# URC.net
KiCad netlist of a schematic drawn in EAGLE
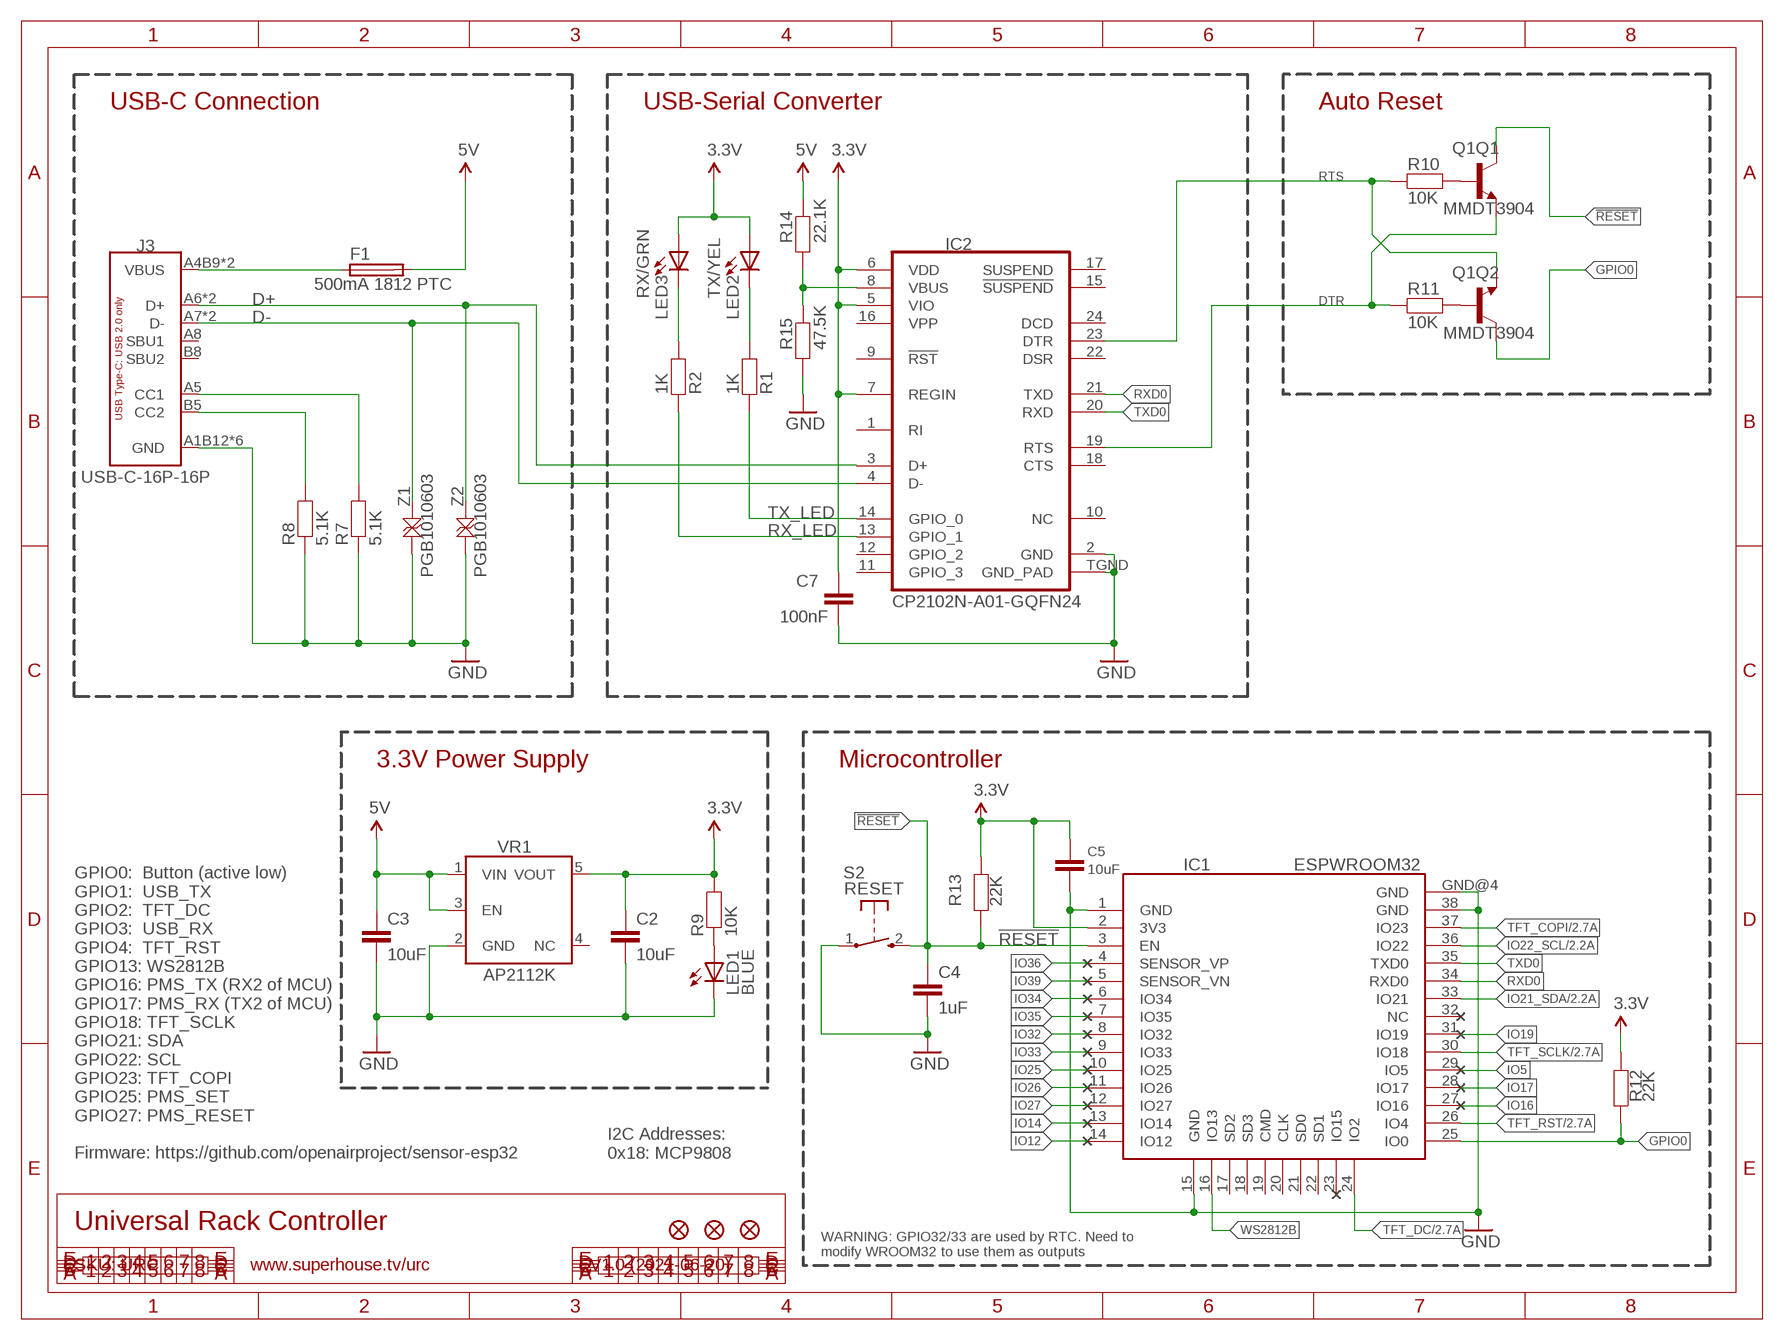
[diagram p0: schematic, sheet 1]
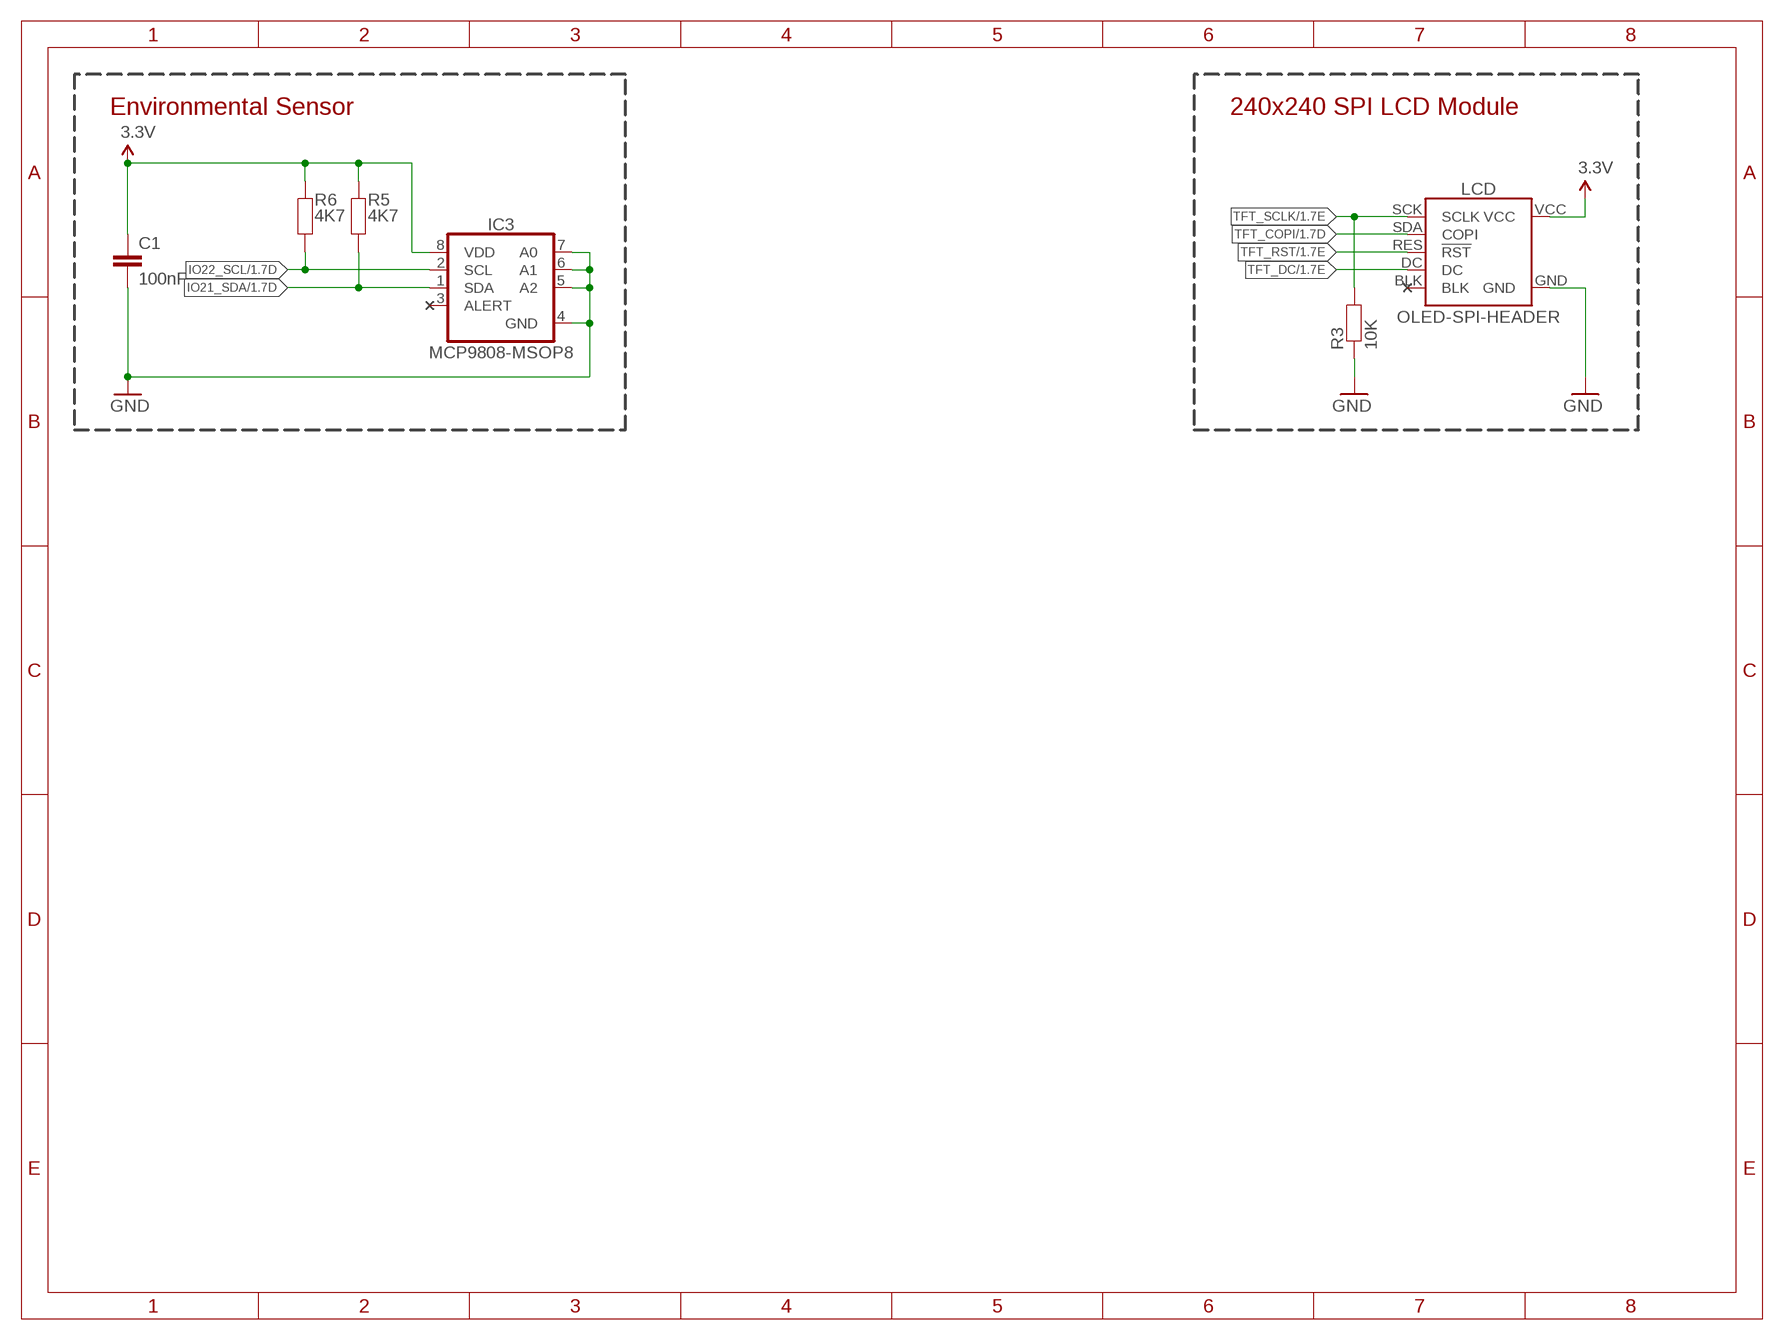
[diagram p1: schematic, sheet 2]

(export (version "E")
  (design (tool "Eeschema 10.0.6"))
  (components
    (comp (ref "C1")
      (value "100nF")
      (footprint "eagle-import:C0603")
      (libsource (lib "eagle-import") (part "CAP0603"))
    )
    (comp (ref "IC3")
      (value "MCP9808-MSOP8")
      (footprint "eagle-import:MSOP-8")
      (libsource (lib "eagle-import") (part "MCP9808-MSOP8"))
    )
    (comp (ref "LCD")
      (value "OLED-SPI-HEADER")
      (footprint "eagle-import:OLED-240X240-1.3-HEADER")
      (libsource (lib "eagle-import") (part "OLED-SPI-HEADER"))
    )
    (comp (ref "R3")
      (value "10K")
      (footprint "eagle-import:R0603")
      (libsource (lib "eagle-import") (part "SuperHouse-Resistors_28961094_RESISTOR0603"))
    )
    (comp (ref "R5")
      (value "4K7")
      (footprint "eagle-import:R0603")
      (libsource (lib "eagle-import") (part "RESISTOR0603"))
    )
    (comp (ref "R6")
      (value "4K7")
      (footprint "eagle-import:R0603")
      (libsource (lib "eagle-import") (part "RESISTOR0603"))
    )
    (comp (ref "C2")
      (value "10uF")
      (footprint "eagle-import:C0805")
      (libsource (lib "eagle-import") (part "CAP0805"))
    )
    (comp (ref "C3")
      (value "10uF")
      (footprint "eagle-import:C0805")
      (libsource (lib "eagle-import") (part "CAP0805"))
    )
    (comp (ref "C4")
      (value "1uF")
      (footprint "eagle-import:C0603")
      (libsource (lib "eagle-import") (part "CAP0603"))
    )
    (comp (ref "C5")
      (value "10uF")
      (footprint "eagle-import:C0805")
      (libsource (lib "eagle-import") (part "CAP0805"))
    )
    (comp (ref "C7")
      (value "100nF")
      (footprint "eagle-import:C0603")
      (libsource (lib "eagle-import") (part "CAP0603"))
    )
    (comp (ref "F1")
      (value "500mA 1812 PTC")
      (footprint "eagle-import:1812")
      (libsource (lib "eagle-import") (part "PTC050"))
    )
    (comp (ref "IC1")
      (value "ESPWROOM32")
      (footprint "eagle-import:ESPWROOM32")
      (libsource (lib "eagle-import") (part "ESPWROOM32"))
    )
    (comp (ref "IC2")
      (value "CP2102N-A01-GQFN24")
      (footprint "eagle-import:QFN-24")
      (libsource (lib "eagle-import") (part "CP2104"))
    )
    (comp (ref "J3")
      (value "USB-C-16P-16P")
      (footprint "eagle-import:USB-C-16P")
      (libsource (lib "eagle-import") (part "USB-C-16P-16P"))
    )
    (comp (ref "LED1")
      (value "BLUE")
      (footprint "eagle-import:LED-0603")
      (libsource (lib "eagle-import") (part "LED0603"))
    )
    (comp (ref "LED2")
      (value "TX/YEL")
      (footprint "eagle-import:LED-0603")
      (libsource (lib "eagle-import") (part "LED0603"))
    )
    (comp (ref "LED3")
      (value "RX/GRN")
      (footprint "eagle-import:LED-0603")
      (libsource (lib "eagle-import") (part "LED0603"))
    )
    (comp (ref "Q1")
      (value "MMDT3904")
      (footprint "eagle-import:SOT-363")
      (libsource (lib "eagle-import") (part "TRANS_NPN_DUAL-MMDT3904"))
    )
    (comp (ref "R1")
      (value "1K")
      (footprint "eagle-import:R0603")
      (libsource (lib "eagle-import") (part "RESISTOR0603"))
    )
    (comp (ref "R2")
      (value "1K")
      (footprint "eagle-import:R0603")
      (libsource (lib "eagle-import") (part "RESISTOR0603"))
    )
    (comp (ref "R7")
      (value "5.1K")
      (footprint "eagle-import:R0603")
      (libsource (lib "eagle-import") (part "RESISTOR0603"))
    )
    (comp (ref "R8")
      (value "5.1K")
      (footprint "eagle-import:R0603")
      (libsource (lib "eagle-import") (part "RESISTOR0603"))
    )
    (comp (ref "R9")
      (value "10K")
      (footprint "eagle-import:R0603")
      (libsource (lib "eagle-import") (part "RESISTOR0603"))
    )
    (comp (ref "R10")
      (value "10K")
      (footprint "eagle-import:R0603")
      (libsource (lib "eagle-import") (part "RESISTOR0603"))
    )
    (comp (ref "R11")
      (value "10K")
      (footprint "eagle-import:R0603")
      (libsource (lib "eagle-import") (part "RESISTOR0603"))
    )
    (comp (ref "R12")
      (value "22K")
      (footprint "eagle-import:R0603")
      (libsource (lib "eagle-import") (part "RESISTOR0603"))
    )
    (comp (ref "R13")
      (value "22K")
      (footprint "eagle-import:R0603")
      (libsource (lib "eagle-import") (part "RESISTOR0603"))
    )
    (comp (ref "R14")
      (value "22.1K")
      (footprint "eagle-import:R0603")
      (libsource (lib "eagle-import") (part "RESISTOR0603"))
    )
    (comp (ref "R15")
      (value "47.5K")
      (footprint "eagle-import:R0603")
      (libsource (lib "eagle-import") (part "RESISTOR0603"))
    )
    (comp (ref "S2")
      (value "RESET")
      (footprint "eagle-import:TACTILE_SMT_3X4X2")
      (libsource (lib "eagle-import") (part "TAC_SWITCH_2PINSMT"))
    )
    (comp (ref "U$23")
      (value "FIDUCIAL1X2")
      (footprint "eagle-import:FIDUCIAL-1X2")
      (libsource (lib "eagle-import") (part "FIDUCIAL1X2"))
    )
    (comp (ref "U$24")
      (value "FIDUCIAL1X2")
      (footprint "eagle-import:FIDUCIAL-1X2")
      (libsource (lib "eagle-import") (part "FIDUCIAL1X2"))
    )
    (comp (ref "U$25")
      (value "FIDUCIAL1X2")
      (footprint "eagle-import:FIDUCIAL-1X2")
      (libsource (lib "eagle-import") (part "FIDUCIAL1X2"))
    )
    (comp (ref "VR1")
      (value "AP2112KSOT25")
      (footprint "eagle-import:SOT23-5")
      (libsource (lib "eagle-import") (part "AP2112KSOT25"))
    )
    (comp (ref "Z1")
      (value "PGB1010603")
      (footprint "eagle-import:TVS0603")
      (libsource (lib "eagle-import") (part "TVS0603"))
    )
    (comp (ref "Z2")
      (value "PGB1010603")
      (footprint "eagle-import:TVS0603")
      (libsource (lib "eagle-import") (part "TVS0603"))
    )
  )
  (nets
    (net (code "1") (name "3.3V") (class "Default")
      (node (ref "C1") (pin "1") (pinfunction "1_1") (pintype "passive"))
      (node (ref "C2") (pin "1") (pinfunction "1_1") (pintype "passive"))
      (node (ref "C5") (pin "1") (pinfunction "1_1") (pintype "passive"))
      (node (ref "C7") (pin "1") (pinfunction "1_1") (pintype "passive"))
      (node (ref "IC1") (pin "2") (pinfunction "3V3_2") (pintype "power_in"))
      (node (ref "IC2") (pin "5") (pinfunction "VIO_5") (pintype "bidirectional"))
      (node (ref "IC2") (pin "6") (pinfunction "VDD_6") (pintype "power_in"))
      (node (ref "IC2") (pin "7") (pinfunction "REGIN_7") (pintype "power_in"))
      (node (ref "IC3") (pin "8") (pinfunction "VDD_8") (pintype "bidirectional"))
      (node (ref "LCD") (pin "VCC") (pinfunction "VCC_VCC") (pintype "bidirectional"))
      (node (ref "LED2") (pin "A") (pinfunction "A_A") (pintype "passive"))
      (node (ref "LED3") (pin "A") (pinfunction "A_A") (pintype "passive"))
      (node (ref "R12") (pin "1") (pinfunction "1_1") (pintype "passive"))
      (node (ref "R13") (pin "1") (pinfunction "1_1") (pintype "passive"))
      (node (ref "R5") (pin "2") (pinfunction "2_2") (pintype "passive"))
      (node (ref "R6") (pin "2") (pinfunction "2_2") (pintype "passive"))
      (node (ref "R9") (pin "2") (pinfunction "2_2") (pintype "passive"))
      (node (ref "VR1") (pin "5") (pinfunction "VOUT_5") (pintype "bidirectional"))
    )
    (net (code "2") (name "5V") (class "Default")
      (node (ref "C3") (pin "1") (pinfunction "1_1") (pintype "passive"))
      (node (ref "F1") (pin "2") (pinfunction "2_2") (pintype "passive"))
      (node (ref "R14") (pin "2") (pinfunction "2_2") (pintype "passive"))
      (node (ref "VR1") (pin "1") (pinfunction "VIN_1") (pintype "bidirectional"))
      (node (ref "VR1") (pin "3") (pinfunction "EN_3") (pintype "bidirectional"))
    )
    (net (code "3") (name "D+") (class "Default")
      (node (ref "IC2") (pin "3") (pinfunction "D+_3") (pintype "bidirectional"))
      (node (ref "J3") (pin "A6") (pinfunction "D+_A6") (pintype "bidirectional"))
      (node (ref "J3") (pin "B6") (pinfunction "D+_B6") (pintype "bidirectional"))
      (node (ref "Z2") (pin "2") (pinfunction "2_2") (pintype "passive"))
    )
    (net (code "4") (name "D-") (class "Default")
      (node (ref "IC2") (pin "4") (pinfunction "D-_4") (pintype "bidirectional"))
      (node (ref "J3") (pin "A7") (pinfunction "D-_A7") (pintype "bidirectional"))
      (node (ref "J3") (pin "B7") (pinfunction "D-_B7") (pintype "bidirectional"))
      (node (ref "Z1") (pin "2") (pinfunction "2_2") (pintype "passive"))
    )
    (net (code "5") (name "DTR") (class "Default")
      (node (ref "IC2") (pin "23") (pinfunction "DTR_23") (pintype "output"))
      (node (ref "Q1") (pin "1") (pinfunction "E_1") (pintype "passive"))
      (node (ref "R10") (pin "1") (pinfunction "1_1") (pintype "passive"))
    )
    (net (code "6") (name "GND") (class "Default")
      (node (ref "C1") (pin "2") (pinfunction "2_2") (pintype "passive"))
      (node (ref "C2") (pin "2") (pinfunction "2_2") (pintype "passive"))
      (node (ref "C3") (pin "2") (pinfunction "2_2") (pintype "passive"))
      (node (ref "C4") (pin "2") (pinfunction "2_2") (pintype "passive"))
      (node (ref "C5") (pin "2") (pinfunction "2_2") (pintype "passive"))
      (node (ref "C7") (pin "2") (pinfunction "2_2") (pintype "passive"))
      (node (ref "IC1") (pin "1") (pinfunction "GND_1") (pintype "power_in"))
      (node (ref "IC1") (pin "15") (pinfunction "GND_15") (pintype "power_in"))
      (node (ref "IC1") (pin "38") (pinfunction "GND_38") (pintype "power_in"))
      (node (ref "IC1") (pin "GND@4") (pinfunction "GND_GND@4") (pintype "power_in"))
      (node (ref "IC2") (pin "2") (pinfunction "GND_2") (pintype "power_in"))
      (node (ref "IC2") (pin "TGND") (pinfunction "GND_PAD_TGND") (pintype "power_in"))
      (node (ref "IC3") (pin "4") (pinfunction "GND_4") (pintype "bidirectional"))
      (node (ref "IC3") (pin "5") (pinfunction "A2_5") (pintype "bidirectional"))
      (node (ref "IC3") (pin "6") (pinfunction "A1_6") (pintype "bidirectional"))
      (node (ref "IC3") (pin "7") (pinfunction "A0_7") (pintype "bidirectional"))
      (node (ref "J3") (pin "A12B1") (pinfunction "GND_A12B1") (pintype "power_in"))
      (node (ref "J3") (pin "A1B12") (pinfunction "GND_A1B12") (pintype "power_in"))
      (node (ref "J3") (pin "FIX1") (pinfunction "GND_FIX1") (pintype "power_in"))
      (node (ref "J3") (pin "FIX2") (pinfunction "GND_FIX2") (pintype "power_in"))
      (node (ref "J3") (pin "FIX3") (pinfunction "GND_FIX3") (pintype "power_in"))
      (node (ref "J3") (pin "FIX4") (pinfunction "GND_FIX4") (pintype "power_in"))
      (node (ref "LCD") (pin "GND") (pinfunction "GND_GND") (pintype "bidirectional"))
      (node (ref "LED1") (pin "C") (pinfunction "C_C") (pintype "passive"))
      (node (ref "R15") (pin "1") (pinfunction "1_1") (pintype "passive"))
      (node (ref "R3") (pin "1") (pinfunction "1_1") (pintype "passive"))
      (node (ref "R7") (pin "1") (pinfunction "1_1") (pintype "passive"))
      (node (ref "R8") (pin "1") (pinfunction "1_1") (pintype "passive"))
      (node (ref "S2") (pin "1") (pinfunction "P_1") (pintype "passive"))
      (node (ref "VR1") (pin "2") (pinfunction "GND_2") (pintype "bidirectional"))
      (node (ref "Z1") (pin "1") (pinfunction "1_1") (pintype "passive"))
      (node (ref "Z2") (pin "1") (pinfunction "1_1") (pintype "passive"))
    )
    (net (code "7") (name "GPIO0") (class "Default")
      (node (ref "IC1") (pin "25") (pinfunction "IO0_25") (pintype "bidirectional"))
      (node (ref "Q1") (pin "6") (pinfunction "C_6") (pintype "passive"))
      (node (ref "R12") (pin "2") (pinfunction "2_2") (pintype "passive"))
    )
    (net (code "8") (name "IO5") (class "Default")
      (node (ref "IC1") (pin "29") (pinfunction "IO5_29") (pintype "bidirectional"))
    )
    (net (code "9") (name "IO12") (class "Default")
      (node (ref "IC1") (pin "14") (pinfunction "IO12_14") (pintype "bidirectional"))
    )
    (net (code "10") (name "IO14") (class "Default")
      (node (ref "IC1") (pin "13") (pinfunction "IO14_13") (pintype "bidirectional"))
    )
    (net (code "11") (name "IO16") (class "Default")
      (node (ref "IC1") (pin "27") (pinfunction "IO16_27") (pintype "bidirectional"))
    )
    (net (code "12") (name "IO17") (class "Default")
      (node (ref "IC1") (pin "28") (pinfunction "IO17_28") (pintype "bidirectional"))
    )
    (net (code "13") (name "IO19") (class "Default")
      (node (ref "IC1") (pin "31") (pinfunction "IO19_31") (pintype "bidirectional"))
    )
    (net (code "14") (name "IO21_SDA") (class "Default")
      (node (ref "IC1") (pin "33") (pinfunction "IO21_33") (pintype "bidirectional"))
      (node (ref "IC3") (pin "1") (pinfunction "SDA_1") (pintype "bidirectional"))
      (node (ref "R5") (pin "1") (pinfunction "1_1") (pintype "passive"))
    )
    (net (code "15") (name "IO22_SCL") (class "Default")
      (node (ref "IC1") (pin "36") (pinfunction "IO22_36") (pintype "bidirectional"))
      (node (ref "IC3") (pin "2") (pinfunction "SCL_2") (pintype "bidirectional"))
      (node (ref "R6") (pin "1") (pinfunction "1_1") (pintype "passive"))
    )
    (net (code "16") (name "IO25") (class "Default")
      (node (ref "IC1") (pin "10") (pinfunction "IO25_10") (pintype "bidirectional"))
    )
    (net (code "17") (name "IO26") (class "Default")
      (node (ref "IC1") (pin "11") (pinfunction "IO26_11") (pintype "bidirectional"))
    )
    (net (code "18") (name "IO27") (class "Default")
      (node (ref "IC1") (pin "12") (pinfunction "IO27_12") (pintype "bidirectional"))
    )
    (net (code "19") (name "IO32") (class "Default")
      (node (ref "IC1") (pin "8") (pinfunction "IO32_8") (pintype "bidirectional"))
    )
    (net (code "20") (name "IO33") (class "Default")
      (node (ref "IC1") (pin "9") (pinfunction "IO33_9") (pintype "bidirectional"))
    )
    (net (code "21") (name "IO34") (class "Default")
      (node (ref "IC1") (pin "6") (pinfunction "IO34_6") (pintype "bidirectional"))
    )
    (net (code "22") (name "IO35") (class "Default")
      (node (ref "IC1") (pin "7") (pinfunction "IO35_7") (pintype "bidirectional"))
    )
    (net (code "23") (name "IO36") (class "Default")
      (node (ref "IC1") (pin "4") (pinfunction "SENSOR_VP_4") (pintype "bidirectional"))
    )
    (net (code "24") (name "IO39") (class "Default")
      (node (ref "IC1") (pin "5") (pinfunction "SENSOR_VN_5") (pintype "bidirectional"))
    )
    (net (code "25") (name "Net-(F1-Pad1)") (class "Default")
      (node (ref "F1") (pin "1") (pinfunction "1_1") (pintype "passive"))
      (node (ref "J3") (pin "A4B9") (pinfunction "VBUS_A4B9") (pintype "power_in"))
      (node (ref "J3") (pin "A9B4") (pinfunction "VBUS_A9B4") (pintype "power_in"))
    )
    (net (code "26") (name "Net-(IC2-VBUS)") (class "Default")
      (node (ref "IC2") (pin "8") (pinfunction "VBUS_8") (pintype "bidirectional"))
      (node (ref "R14") (pin "1") (pinfunction "1_1") (pintype "passive"))
      (node (ref "R15") (pin "2") (pinfunction "2_2") (pintype "passive"))
    )
    (net (code "27") (name "Net-(J3-CC1)") (class "Default")
      (node (ref "J3") (pin "A5") (pinfunction "CC1_A5") (pintype "bidirectional"))
      (node (ref "R7") (pin "2") (pinfunction "2_2") (pintype "passive"))
    )
    (net (code "28") (name "Net-(J3-CC2)") (class "Default")
      (node (ref "J3") (pin "B5") (pinfunction "CC2_B5") (pintype "bidirectional"))
      (node (ref "R8") (pin "2") (pinfunction "2_2") (pintype "passive"))
    )
    (net (code "29") (name "Net-(LED1-PadA)") (class "Default")
      (node (ref "LED1") (pin "A") (pinfunction "A_A") (pintype "passive"))
      (node (ref "R9") (pin "1") (pinfunction "1_1") (pintype "passive"))
    )
    (net (code "30") (name "Net-(LED2-PadC)") (class "Default")
      (node (ref "LED2") (pin "C") (pinfunction "C_C") (pintype "passive"))
      (node (ref "R1") (pin "2") (pinfunction "2_2") (pintype "passive"))
    )
    (net (code "31") (name "Net-(LED3-PadC)") (class "Default")
      (node (ref "LED3") (pin "C") (pinfunction "C_C") (pintype "passive"))
      (node (ref "R2") (pin "2") (pinfunction "2_2") (pintype "passive"))
    )
    (net (code "32") (name "Net-(Q1A-B)") (class "Default")
      (node (ref "Q1") (pin "5") (pinfunction "B_5") (pintype "passive"))
      (node (ref "R10") (pin "2") (pinfunction "2_2") (pintype "passive"))
    )
    (net (code "33") (name "Net-(Q1B-B)") (class "Default")
      (node (ref "Q1") (pin "2") (pinfunction "B_2") (pintype "passive"))
      (node (ref "R11") (pin "2") (pinfunction "2_2") (pintype "passive"))
    )
    (net (code "34") (name "RTS") (class "Default")
      (node (ref "IC2") (pin "19") (pinfunction "RTS_19") (pintype "output"))
      (node (ref "Q1") (pin "4") (pinfunction "E_4") (pintype "passive"))
      (node (ref "R11") (pin "1") (pinfunction "1_1") (pintype "passive"))
    )
    (net (code "35") (name "RXD0") (class "Default")
      (node (ref "IC1") (pin "34") (pinfunction "RXD0_34") (pintype "bidirectional"))
      (node (ref "IC2") (pin "21") (pinfunction "TXD_21") (pintype "output"))
    )
    (net (code "36") (name "RX_LED") (class "Default")
      (node (ref "IC2") (pin "13") (pinfunction "GPIO_1_13") (pintype "bidirectional"))
      (node (ref "R2") (pin "1") (pinfunction "1_1") (pintype "passive"))
    )
    (net (code "37") (name "TFT_COPI") (class "Default")
      (node (ref "IC1") (pin "37") (pinfunction "IO23_37") (pintype "bidirectional"))
      (node (ref "LCD") (pin "SDA") (pinfunction "COPI_SDA") (pintype "bidirectional"))
    )
    (net (code "38") (name "TFT_DC") (class "Default")
      (node (ref "IC1") (pin "24") (pinfunction "IO2_24") (pintype "bidirectional"))
      (node (ref "LCD") (pin "DC") (pinfunction "DC_DC") (pintype "bidirectional"))
    )
    (net (code "39") (name "TFT_RST") (class "Default")
      (node (ref "IC1") (pin "26") (pinfunction "IO4_26") (pintype "bidirectional"))
      (node (ref "LCD") (pin "RES") (pinfunction "~{RST}_RES") (pintype "bidirectional"))
    )
    (net (code "40") (name "TFT_SCLK") (class "Default")
      (node (ref "IC1") (pin "30") (pinfunction "IO18_30") (pintype "bidirectional"))
      (node (ref "LCD") (pin "SCK") (pinfunction "SCLK_SCK") (pintype "bidirectional"))
      (node (ref "R3") (pin "2") (pinfunction "2_2") (pintype "passive"))
    )
    (net (code "41") (name "TXD0") (class "Default")
      (node (ref "IC1") (pin "35") (pinfunction "TXD0_35") (pintype "bidirectional"))
      (node (ref "IC2") (pin "20") (pinfunction "RXD_20") (pintype "input"))
    )
    (net (code "42") (name "TX_LED") (class "Default")
      (node (ref "IC2") (pin "14") (pinfunction "GPIO_0_14") (pintype "bidirectional"))
      (node (ref "R1") (pin "1") (pinfunction "1_1") (pintype "passive"))
    )
    (net (code "43") (name "WS2812B") (class "Default")
      (node (ref "IC1") (pin "16") (pinfunction "IO13_16") (pintype "bidirectional"))
    )
    (net (code "44") (name "unconnected-(IC1-CLK-Pad20)") (class "Default")
      (node (ref "IC1") (pin "20") (pinfunction "CLK_20") (pintype "bidirectional"))
    )
    (net (code "45") (name "unconnected-(IC1-CMD-Pad19)") (class "Default")
      (node (ref "IC1") (pin "19") (pinfunction "CMD_19") (pintype "bidirectional"))
    )
    (net (code "46") (name "unconnected-(IC1-IO15-Pad23)") (class "Default")
      (node (ref "IC1") (pin "23") (pinfunction "IO15_23") (pintype "bidirectional"))
    )
    (net (code "47") (name "unconnected-(IC1-NC-Pad32)") (class "Default")
      (node (ref "IC1") (pin "32") (pinfunction "NC_32") (pintype "bidirectional"))
    )
    (net (code "48") (name "unconnected-(IC1-SD0-Pad21)") (class "Default")
      (node (ref "IC1") (pin "21") (pinfunction "SD0_21") (pintype "bidirectional"))
    )
    (net (code "49") (name "unconnected-(IC1-SD1-Pad22)") (class "Default")
      (node (ref "IC1") (pin "22") (pinfunction "SD1_22") (pintype "bidirectional"))
    )
    (net (code "50") (name "unconnected-(IC1-SD2-Pad17)") (class "Default")
      (node (ref "IC1") (pin "17") (pinfunction "SD2_17") (pintype "bidirectional"))
    )
    (net (code "51") (name "unconnected-(IC1-SD3-Pad18)") (class "Default")
      (node (ref "IC1") (pin "18") (pinfunction "SD3_18") (pintype "bidirectional"))
    )
    (net (code "52") (name "unconnected-(IC2-CTS-Pad18)") (class "Default")
      (node (ref "IC2") (pin "18") (pinfunction "CTS_18") (pintype "input"))
    )
    (net (code "53") (name "unconnected-(IC2-DCD-Pad24)") (class "Default")
      (node (ref "IC2") (pin "24") (pinfunction "DCD_24") (pintype "input"))
    )
    (net (code "54") (name "unconnected-(IC2-DSR-Pad22)") (class "Default")
      (node (ref "IC2") (pin "22") (pinfunction "DSR_22") (pintype "input"))
    )
    (net (code "55") (name "unconnected-(IC2-GPIO_2-Pad12)") (class "Default")
      (node (ref "IC2") (pin "12") (pinfunction "GPIO_2_12") (pintype "bidirectional"))
    )
    (net (code "56") (name "unconnected-(IC2-GPIO_3-Pad11)") (class "Default")
      (node (ref "IC2") (pin "11") (pinfunction "GPIO_3_11") (pintype "bidirectional"))
    )
    (net (code "57") (name "unconnected-(IC2-NC-Pad10)") (class "Default")
      (node (ref "IC2") (pin "10") (pinfunction "NC_10") (pintype "input"))
    )
    (net (code "58") (name "unconnected-(IC2-RI-Pad1)") (class "Default")
      (node (ref "IC2") (pin "1") (pinfunction "RI_1") (pintype "input"))
    )
    (net (code "59") (name "unconnected-(IC2-SUSPEND-Pad17)") (class "Default")
      (node (ref "IC2") (pin "17") (pinfunction "SUSPEND_17") (pintype "output"))
    )
    (net (code "60") (name "unconnected-(IC2-VPP-Pad16)") (class "Default")
      (node (ref "IC2") (pin "16") (pinfunction "VPP_16") (pintype "bidirectional"))
    )
    (net (code "61") (name "unconnected-(IC2-~{RST}-Pad9)") (class "Default")
      (node (ref "IC2") (pin "9") (pinfunction "~{RST}_9") (pintype "bidirectional"))
    )
    (net (code "62") (name "unconnected-(IC2-~{SUSPEND}-Pad15)") (class "Default")
      (node (ref "IC2") (pin "15") (pinfunction "~{SUSPEND}_15") (pintype "output"))
    )
    (net (code "63") (name "unconnected-(IC3-ALERT-Pad3)") (class "Default")
      (node (ref "IC3") (pin "3") (pinfunction "ALERT_3") (pintype "bidirectional"))
    )
    (net (code "64") (name "unconnected-(J3-SBU1-PadA8)") (class "Default")
      (node (ref "J3") (pin "A8") (pinfunction "SBU1_A8") (pintype "bidirectional"))
    )
    (net (code "65") (name "unconnected-(J3-SBU2-PadB8)") (class "Default")
      (node (ref "J3") (pin "B8") (pinfunction "SBU2_B8") (pintype "bidirectional"))
    )
    (net (code "66") (name "unconnected-(LCD-PadBLK)") (class "Default")
      (node (ref "LCD") (pin "BLK") (pinfunction "BLK_BLK") (pintype "bidirectional"))
    )
    (net (code "67") (name "unconnected-(VR1-NC-Pad4)") (class "Default")
      (node (ref "VR1") (pin "4") (pinfunction "NC_4") (pintype "bidirectional"))
    )
    (net (code "68") (name "~{RESET}") (class "Default")
      (node (ref "C4") (pin "1") (pinfunction "1_1") (pintype "passive"))
      (node (ref "IC1") (pin "3") (pinfunction "EN_3") (pintype "bidirectional"))
      (node (ref "Q1") (pin "3") (pinfunction "C_3") (pintype "passive"))
      (node (ref "R13") (pin "2") (pinfunction "2_2") (pintype "passive"))
      (node (ref "S2") (pin "2") (pinfunction "S_2") (pintype "passive"))
    )
  )
)
